# Sheet3.net
KiCad netlist of a schematic drawn in Altium Designer
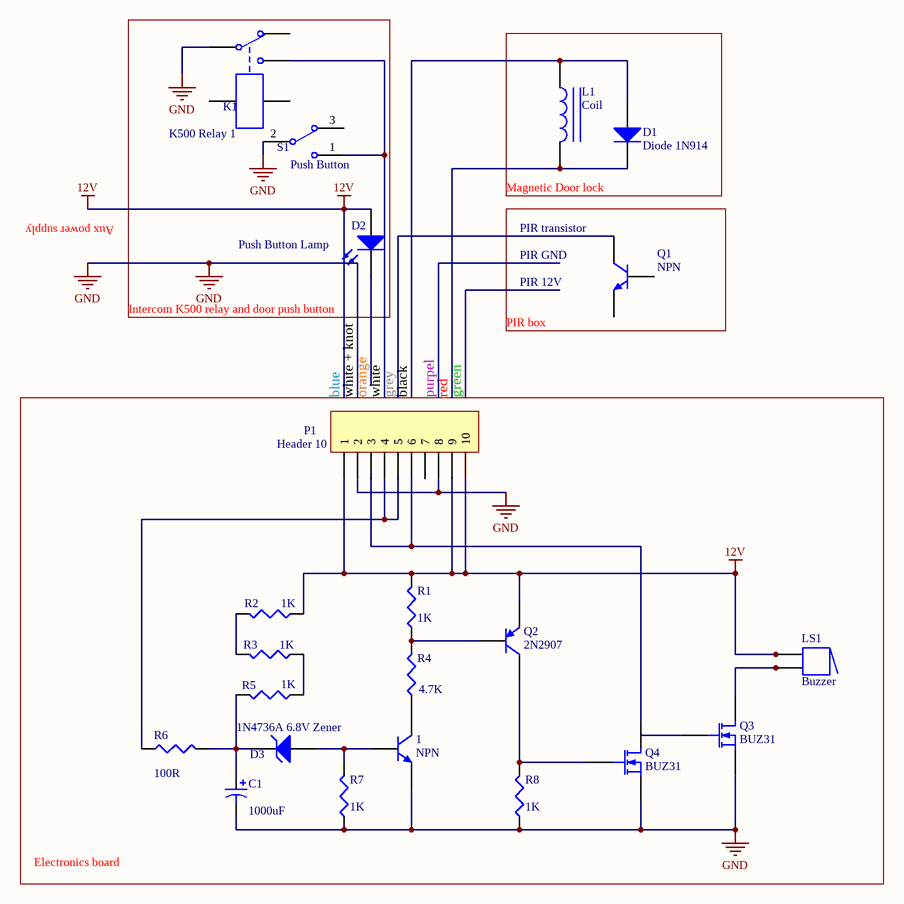
[diagram p0: Sheet3.SchDoc]

(export (version "E")
  (design (tool "Eeschema 10.0.6"))
  (components
    (comp (ref "1")
      (value "NPN")
      (footprint "TO-226-AA")
      (description "NPN Bipolar Transistor")
      (fields (field (name "PUBLISHER") "Altium Limited"))
      (libsource (lib "Miscellaneous Devices") (part "NPN"))
    )
    (comp (ref "C1")
      (value "1000uF")
      (footprint "RB7.6-15")
      (description "Polarized Capacitor (Radial)")
      (fields (field (name "Comment") "Cap Pol1") (field (name "PUBLISHER") "Altium Limited"))
      (libsource (lib "Miscellaneous Devices") (part "Cap Pol1"))
    )
    (comp (ref "D1")
      (value "Diode 1N914")
      (footprint "DO-35")
      (description "High Conductance Fast Diode")
      (fields (field (name "PUBLISHER") "Altium Limited"))
      (libsource (lib "Miscellaneous Devices") (part "Diode 1N914"))
    )
    (comp (ref "D2")
      (value "Push Button Lamp")
      (footprint "LED-1")
      (description "Typical RED GaAs LED")
      (fields (field (name "PUBLISHER") "Altium Limited"))
      (libsource (lib "Miscellaneous Devices") (part "LED1"))
    )
    (comp (ref "D3")
      (value "1N4736A 6.8V Zener")
      (footprint "DIODE-0.7")
      (description "Zener Diode")
      (fields (field (name "PUBLISHER") "Altium Limited"))
      (libsource (lib "Miscellaneous Devices") (part "D Zener"))
    )
    (comp (ref "K1")
      (value "K500 Relay 1")
      (footprint "MODULE5B")
      (description "Single-Pole Dual-Throw Relay")
      (fields (field (name "PUBLISHER") "Altium Limited"))
      (libsource (lib "Miscellaneous Devices") (part "Relay-SPDT"))
    )
    (comp (ref "L1")
      (value "Coil")
      (footprint "AXIAL-0.9")
      (description "Magnetic-Core Inductor")
      (fields (field (name "PUBLISHER") "Altium Limited"))
      (libsource (lib "Miscellaneous Devices") (part "Inductor Iron"))
    )
    (comp (ref "LS1")
      (value "Buzzer")
      (footprint "ABSM-1574")
      (description "Magnetic Transducer Buzzer")
      (fields (field (name "PUBLISHER") "Altium Limited"))
      (libsource (lib "Miscellaneous Devices") (part "Buzzer"))
    )
    (comp (ref "P1")
      (value "Header 10")
      (footprint "HDR1X10")
      (description "Header, 10-Pin")
      (fields (field (name "PUBLISHER") "Altium Limited"))
      (libsource (lib "Miscellaneous Connectors") (part "Header 10"))
    )
    (comp (ref "Q1")
      (value "NPN")
      (footprint "TO-226-AA")
      (description "NPN Bipolar Transistor")
      (fields (field (name "PUBLISHER") "Altium Limited"))
      (libsource (lib "Miscellaneous Devices") (part "NPN"))
    )
    (comp (ref "Q2")
      (value "2N2907")
      (footprint "SOT-23B_N")
      (description "PNP Bipolar Transistor")
      (fields (field (name "PUBLISHER") "Altium Limited"))
      (libsource (lib "Miscellaneous Devices") (part "PNP"))
    )
    (comp (ref "Q3")
      (value "BUZ31")
      (footprint "E3")
      (description "N-Channel MOSFET")
      (fields (field (name "PUBLISHER") "Altium Limited"))
      (libsource (lib "Miscellaneous Devices") (part "MOSFET-N"))
    )
    (comp (ref "Q4")
      (value "BUZ31")
      (footprint "E3")
      (description "N-Channel MOSFET")
      (fields (field (name "PUBLISHER") "Altium Limited"))
      (libsource (lib "Miscellaneous Devices") (part "MOSFET-N"))
    )
    (comp (ref "R1")
      (value "1K")
      (footprint "J1-0603")
      (description "Resistor")
      (fields (field (name "Comment") "Res3") (field (name "PUBLISHER") "Altium Limited"))
      (libsource (lib "Miscellaneous Devices") (part "Res3"))
    )
    (comp (ref "R2")
      (value "1K")
      (footprint "J1-0603")
      (description "Resistor")
      (fields (field (name "Comment") "Res3") (field (name "PUBLISHER") "Altium Limited"))
      (libsource (lib "Miscellaneous Devices") (part "Res3"))
    )
    (comp (ref "R3")
      (value "1K")
      (footprint "J1-0603")
      (description "Resistor")
      (fields (field (name "Comment") "Res3") (field (name "PUBLISHER") "Altium Limited"))
      (libsource (lib "Miscellaneous Devices") (part "Res3"))
    )
    (comp (ref "R4")
      (value "4.7K")
      (footprint "J1-0603")
      (description "Resistor")
      (fields (field (name "Comment") "Res3") (field (name "PUBLISHER") "Altium Limited"))
      (libsource (lib "Miscellaneous Devices") (part "Res3"))
    )
    (comp (ref "R5")
      (value "1K")
      (footprint "J1-0603")
      (description "Resistor")
      (fields (field (name "Comment") "Res3") (field (name "PUBLISHER") "Altium Limited"))
      (libsource (lib "Miscellaneous Devices") (part "Res3"))
    )
    (comp (ref "R6")
      (value "100R")
      (footprint "J1-0603")
      (description "Resistor")
      (fields (field (name "Comment") "Res3") (field (name "PUBLISHER") "Altium Limited"))
      (libsource (lib "Miscellaneous Devices") (part "Res3"))
    )
    (comp (ref "R7")
      (value "1K")
      (footprint "J1-0603")
      (description "Resistor")
      (fields (field (name "Comment") "Res3") (field (name "PUBLISHER") "Altium Limited"))
      (libsource (lib "Miscellaneous Devices") (part "Res3"))
    )
    (comp (ref "R8")
      (value "1K")
      (footprint "J1-0603")
      (description "Resistor")
      (fields (field (name "Comment") "Res3") (field (name "PUBLISHER") "Altium Limited"))
      (libsource (lib "Miscellaneous Devices") (part "Res3"))
    )
    (comp (ref "S1")
      (value "Push Button")
      (footprint "TL36WW15050")
      (description "SPDT Subminiature Toggle Switch, Right Angle Mounting, Vertical Actuation")
      (fields (field (name "PUBLISHER") "Altium Limited"))
      (libsource (lib "Miscellaneous Devices") (part "SW-SPDT"))
    )
  )
  (nets
    (net (code "1") (name "12V") (class "Default")
      (node (ref "D2") (pin "1") (pinfunction "A_1") (pintype "passive"))
      (node (ref "LS1") (pin "1") (pinfunction "1_1") (pintype "passive"))
      (node (ref "LS1") (pin "1A") (pinfunction "1A_1A") (pintype "passive"))
      (node (ref "P1") (pin "1") (pinfunction "1_1") (pintype "passive"))
      (node (ref "P1") (pin "10") (pinfunction "10_10") (pintype "passive"))
      (node (ref "P1") (pin "9") (pinfunction "9_9") (pintype "passive"))
      (node (ref "Q2") (pin "3") (pinfunction "E_3") (pintype "passive"))
      (node (ref "R1") (pin "2") (pinfunction "2_2") (pintype "passive"))
      (node (ref "R2") (pin "1") (pinfunction "1_1") (pintype "passive"))
    )
    (net (code "2") (name "GND") (class "Default")
      (node (ref "1") (pin "3") (pinfunction "E_3") (pintype "passive"))
      (node (ref "C1") (pin "2") (pinfunction "2_2") (pintype "passive"))
      (node (ref "K1") (pin "1") (pinfunction "1_1") (pintype "passive"))
      (node (ref "P1") (pin "2") (pinfunction "2_2") (pintype "passive"))
      (node (ref "P1") (pin "8") (pinfunction "8_8") (pintype "passive"))
      (node (ref "Q3") (pin "3") (pinfunction "S_3") (pintype "passive"))
      (node (ref "Q4") (pin "3") (pinfunction "S_3") (pintype "passive"))
      (node (ref "R7") (pin "1") (pinfunction "1_1") (pintype "passive"))
      (node (ref "R8") (pin "1") (pinfunction "1_1") (pintype "passive"))
      (node (ref "S1") (pin "2") (pinfunction "2_2") (pintype "passive"))
    )
    (net (code "3") (name "Net-(1-B)") (class "Default")
      (node (ref "1") (pin "2") (pinfunction "B_2") (pintype "passive"))
      (node (ref "D3") (pin "1") (pinfunction "A_1") (pintype "passive"))
      (node (ref "R7") (pin "2") (pinfunction "2_2") (pintype "passive"))
    )
    (net (code "4") (name "Net-(1-C)") (class "Default")
      (node (ref "1") (pin "1") (pinfunction "C_1") (pintype "passive"))
      (node (ref "R4") (pin "1") (pinfunction "1_1") (pintype "passive"))
    )
    (net (code "5") (name "Net-(D1-A)") (class "Default")
      (node (ref "D1") (pin "1") (pinfunction "A_1") (pintype "passive"))
      (node (ref "L1") (pin "1") (pinfunction "1_1") (pintype "passive"))
    )
    (net (code "6") (name "Net-(D1-K)") (class "Default")
      (node (ref "D1") (pin "2") (pinfunction "K_2") (pintype "passive"))
      (node (ref "L1") (pin "2") (pinfunction "2_2") (pintype "passive"))
    )
    (net (code "7") (name "Net-(D3-K)") (class "Default")
      (node (ref "C1") (pin "1") (pinfunction "1_1") (pintype "passive"))
      (node (ref "D3") (pin "2") (pinfunction "K_2") (pintype "passive"))
      (node (ref "R5") (pin "2") (pinfunction "2_2") (pintype "passive"))
      (node (ref "R6") (pin "2") (pinfunction "2_2") (pintype "passive"))
    )
    (net (code "8") (name "Net-(K1-Pad3)") (class "Default")
      (node (ref "K1") (pin "3") (pinfunction "3_3") (pintype "passive"))
      (node (ref "S1") (pin "1") (pinfunction "1_1") (pintype "passive"))
    )
    (net (code "9") (name "Net-(P1-Pad4)") (class "Default")
      (node (ref "P1") (pin "4") (pinfunction "4_4") (pintype "passive"))
      (node (ref "P1") (pin "5") (pinfunction "5_5") (pintype "passive"))
      (node (ref "R6") (pin "1") (pinfunction "1_1") (pintype "passive"))
    )
    (net (code "10") (name "Net-(Q2-B)") (class "Default")
      (node (ref "Q2") (pin "2") (pinfunction "B_2") (pintype "passive"))
      (node (ref "R1") (pin "1") (pinfunction "1_1") (pintype "passive"))
      (node (ref "R4") (pin "2") (pinfunction "2_2") (pintype "passive"))
    )
    (net (code "11") (name "Net-(Q2-C)") (class "Default")
      (node (ref "Q2") (pin "1") (pinfunction "C_1") (pintype "passive"))
      (node (ref "Q4") (pin "2") (pinfunction "G_2") (pintype "passive"))
      (node (ref "R8") (pin "2") (pinfunction "2_2") (pintype "passive"))
    )
    (net (code "12") (name "Net-(Q3-D)") (class "Default")
      (node (ref "LS1") (pin "2") (pinfunction "2_2") (pintype "passive"))
      (node (ref "LS1") (pin "2A") (pinfunction "2A_2A") (pintype "passive"))
      (node (ref "Q3") (pin "1") (pinfunction "D_1") (pintype "passive"))
    )
    (net (code "13") (name "Net-(Q4-D)") (class "Default")
      (node (ref "P1") (pin "3") (pinfunction "3_3") (pintype "passive"))
      (node (ref "P1") (pin "6") (pinfunction "6_6") (pintype "passive"))
      (node (ref "Q4") (pin "1") (pinfunction "D_1") (pintype "passive"))
    )
    (net (code "14") (name "Net-(R2-Pad2)") (class "Default")
      (node (ref "R2") (pin "2") (pinfunction "2_2") (pintype "passive"))
      (node (ref "R3") (pin "2") (pinfunction "2_2") (pintype "passive"))
    )
    (net (code "15") (name "Net-(R3-Pad1)") (class "Default")
      (node (ref "R3") (pin "1") (pinfunction "1_1") (pintype "passive"))
      (node (ref "R5") (pin "1") (pinfunction "1_1") (pintype "passive"))
    )
    (net (code "16") (name "unconnected-(D2-K-Pad2)") (class "Default")
      (node (ref "D2") (pin "2") (pinfunction "K_2") (pintype "passive"))
    )
    (net (code "17") (name "unconnected-(K1-Pad2)") (class "Default")
      (node (ref "K1") (pin "2") (pinfunction "2_2") (pintype "passive"))
    )
    (net (code "18") (name "unconnected-(K1-Pad4)") (class "Default")
      (node (ref "K1") (pin "4") (pinfunction "4_4") (pintype "passive"))
    )
    (net (code "19") (name "unconnected-(K1-Pad5)") (class "Default")
      (node (ref "K1") (pin "5") (pinfunction "5_5") (pintype "passive"))
    )
    (net (code "20") (name "unconnected-(P1-Pad7)") (class "Default")
      (node (ref "P1") (pin "7") (pinfunction "7_7") (pintype "passive"))
    )
    (net (code "21") (name "unconnected-(Q1-B-Pad2)") (class "Default")
      (node (ref "Q1") (pin "2") (pinfunction "B_2") (pintype "passive"))
    )
    (net (code "22") (name "unconnected-(Q1-C-Pad1)") (class "Default")
      (node (ref "Q1") (pin "1") (pinfunction "C_1") (pintype "passive"))
    )
    (net (code "23") (name "unconnected-(Q1-E-Pad3)") (class "Default")
      (node (ref "Q1") (pin "3") (pinfunction "E_3") (pintype "passive"))
    )
    (net (code "24") (name "unconnected-(Q3-G-Pad2)") (class "Default")
      (node (ref "Q3") (pin "2") (pinfunction "G_2") (pintype "passive"))
    )
    (net (code "25") (name "unconnected-(S1-Pad3)") (class "Default")
      (node (ref "S1") (pin "3") (pinfunction "3_3") (pintype "passive"))
    )
  )
)
